# Grilo.net
KiCad netlist of a schematic drawn in EAGLE
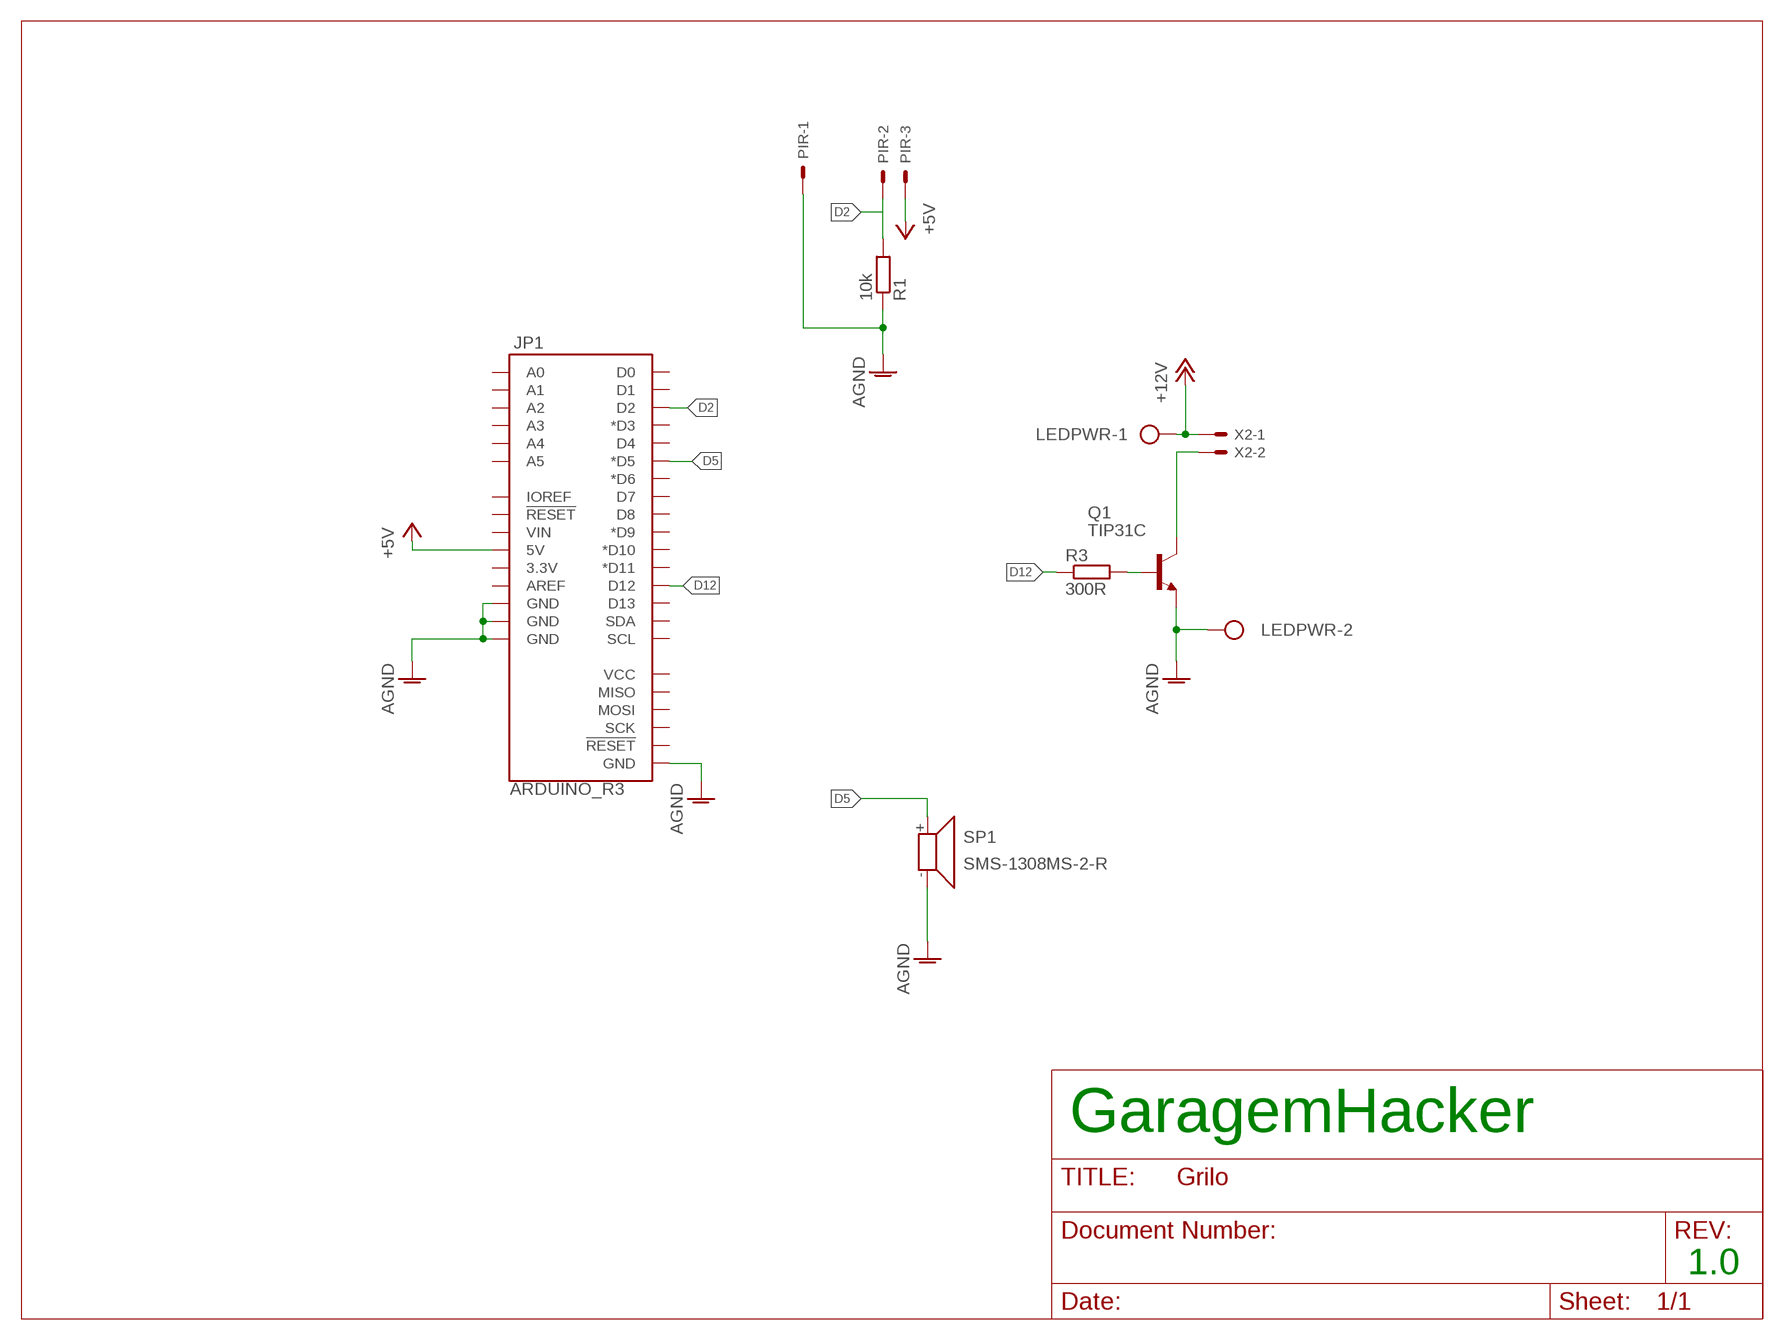
[diagram p0: schematic, sheet 1]

(export (version "E")
  (design (tool "Eeschema 10.0.6"))
  (components
    (comp (ref "JP1")
      (value "ARDUINO_R3")
      (footprint "eagle-import:ARDUINO_R3")
      (libsource (lib "eagle-import") (part "ARDUINO_R3"))
    )
    (comp (ref "LEDPWR")
      (value "AK500/2")
      (footprint "eagle-import:AK500_2")
      (libsource (lib "eagle-import") (part "AK500/2"))
    )
    (comp (ref "PIR")
      (value "KK-156-3")
      (footprint "eagle-import:KK-156-3")
      (libsource (lib "eagle-import") (part "KK-156-3"))
    )
    (comp (ref "Q1")
      (value "TIP31C")
      (footprint "eagle-import:TO220V")
      (libsource (lib "eagle-import") (part "TIP31C"))
    )
    (comp (ref "R1")
      (value "10k")
      (footprint "eagle-import:0207_10")
      (libsource (lib "eagle-import") (part "R-EU_0207/10"))
    )
    (comp (ref "R3")
      (value "300R")
      (footprint "eagle-import:0207_10")
      (libsource (lib "eagle-import") (part "R-EU_0207/10"))
    )
    (comp (ref "SP1")
      (value "SMS-1308MS-2-R")
      (footprint "eagle-import:SMS-1308MS-2-R")
      (libsource (lib "eagle-import") (part "SMS-1308MS-2-R"))
    )
    (comp (ref "X2")
      (value "KK-156-2")
      (footprint "eagle-import:KK-156-2")
      (libsource (lib "eagle-import") (part "KK-156-2"))
    )
  )
  (nets
    (net (code "1") (name "+5V") (class "Default")
      (node (ref "JP1") (pin "5V") (pinfunction "5V_5V") (pintype "bidirectional"))
      (node (ref "PIR") (pin "3") (pinfunction "S_3") (pintype "passive"))
    )
    (net (code "2") (name "+12V") (class "Default")
      (node (ref "LEDPWR") (pin "1") (pinfunction "KL_1") (pintype "passive"))
      (node (ref "X2") (pin "1") (pinfunction "S_1") (pintype "passive"))
    )
    (net (code "3") (name "AGND") (class "Default")
      (node (ref "JP1") (pin "GND@1") (pinfunction "GND_GND@1") (pintype "bidirectional"))
      (node (ref "JP1") (pin "GND@2") (pinfunction "GND_GND@2") (pintype "bidirectional"))
      (node (ref "JP1") (pin "GND@3") (pinfunction "GND_GND@3") (pintype "bidirectional"))
      (node (ref "JP1") (pin "GND@4") (pinfunction "GND_GND@4") (pintype "bidirectional"))
      (node (ref "LEDPWR") (pin "2") (pinfunction "KL_2") (pintype "passive"))
      (node (ref "PIR") (pin "1") (pinfunction "S_1") (pintype "passive"))
      (node (ref "Q1") (pin "3") (pinfunction "E_3") (pintype "passive"))
      (node (ref "R1") (pin "1") (pinfunction "1_1") (pintype "passive"))
      (node (ref "SP1") (pin "-") (pinfunction "2_-") (pintype "passive"))
    )
    (net (code "4") (name "D2") (class "Default")
      (node (ref "JP1") (pin "D2") (pinfunction "D2_D2") (pintype "bidirectional"))
      (node (ref "PIR") (pin "2") (pinfunction "S_2") (pintype "passive"))
      (node (ref "R1") (pin "2") (pinfunction "2_2") (pintype "passive"))
    )
    (net (code "5") (name "D5") (class "Default")
      (node (ref "JP1") (pin "D5") (pinfunction "*D5_D5") (pintype "bidirectional"))
      (node (ref "SP1") (pin "+") (pinfunction "1_+") (pintype "passive"))
    )
    (net (code "6") (name "D12") (class "Default")
      (node (ref "JP1") (pin "D12") (pinfunction "D12_D12") (pintype "bidirectional"))
      (node (ref "R3") (pin "1") (pinfunction "1_1") (pintype "passive"))
    )
    (net (code "7") (name "Net-(Q1-B)") (class "Default")
      (node (ref "Q1") (pin "1") (pinfunction "B_1") (pintype "passive"))
      (node (ref "R3") (pin "2") (pinfunction "2_2") (pintype "passive"))
    )
    (net (code "8") (name "Net-(Q1-C)") (class "Default")
      (node (ref "Q1") (pin "2") (pinfunction "C_2") (pintype "passive"))
      (node (ref "X2") (pin "2") (pinfunction "S_2") (pintype "passive"))
    )
    (net (code "9") (name "unconnected-(JP1-*D3-PadD3)") (class "Default")
      (node (ref "JP1") (pin "D3") (pinfunction "*D3_D3") (pintype "bidirectional"))
    )
    (net (code "10") (name "unconnected-(JP1-*D6-PadD6)") (class "Default")
      (node (ref "JP1") (pin "D6") (pinfunction "*D6_D6") (pintype "bidirectional"))
    )
    (net (code "11") (name "unconnected-(JP1-*D9-PadD9)") (class "Default")
      (node (ref "JP1") (pin "D9") (pinfunction "*D9_D9") (pintype "bidirectional"))
    )
    (net (code "12") (name "unconnected-(JP1-*D10-PadD10)") (class "Default")
      (node (ref "JP1") (pin "D10") (pinfunction "*D10_D10") (pintype "bidirectional"))
    )
    (net (code "13") (name "unconnected-(JP1-*D11-PadD11)") (class "Default")
      (node (ref "JP1") (pin "D11") (pinfunction "*D11_D11") (pintype "bidirectional"))
    )
    (net (code "14") (name "unconnected-(JP1-Pad3.3V)") (class "Default")
      (node (ref "JP1") (pin "3.3V") (pinfunction "3.3V_3.3V") (pintype "bidirectional"))
    )
    (net (code "15") (name "unconnected-(JP1-PadA0)") (class "Default")
      (node (ref "JP1") (pin "A0") (pinfunction "A0_A0") (pintype "bidirectional"))
    )
    (net (code "16") (name "unconnected-(JP1-PadA1)") (class "Default")
      (node (ref "JP1") (pin "A1") (pinfunction "A1_A1") (pintype "bidirectional"))
    )
    (net (code "17") (name "unconnected-(JP1-PadA2)") (class "Default")
      (node (ref "JP1") (pin "A2") (pinfunction "A2_A2") (pintype "bidirectional"))
    )
    (net (code "18") (name "unconnected-(JP1-PadA3)") (class "Default")
      (node (ref "JP1") (pin "A3") (pinfunction "A3_A3") (pintype "bidirectional"))
    )
    (net (code "19") (name "unconnected-(JP1-PadA4)") (class "Default")
      (node (ref "JP1") (pin "A4") (pinfunction "A4_A4") (pintype "bidirectional"))
    )
    (net (code "20") (name "unconnected-(JP1-PadA5)") (class "Default")
      (node (ref "JP1") (pin "A5") (pinfunction "A5_A5") (pintype "bidirectional"))
    )
    (net (code "21") (name "unconnected-(JP1-PadAREF)") (class "Default")
      (node (ref "JP1") (pin "AREF") (pinfunction "AREF_AREF") (pintype "bidirectional"))
    )
    (net (code "22") (name "unconnected-(JP1-PadD0)") (class "Default")
      (node (ref "JP1") (pin "D0") (pinfunction "D0_D0") (pintype "bidirectional"))
    )
    (net (code "23") (name "unconnected-(JP1-PadD1)") (class "Default")
      (node (ref "JP1") (pin "D1") (pinfunction "D1_D1") (pintype "bidirectional"))
    )
    (net (code "24") (name "unconnected-(JP1-PadD4)") (class "Default")
      (node (ref "JP1") (pin "D4") (pinfunction "D4_D4") (pintype "bidirectional"))
    )
    (net (code "25") (name "unconnected-(JP1-PadD7)") (class "Default")
      (node (ref "JP1") (pin "D7") (pinfunction "D7_D7") (pintype "bidirectional"))
    )
    (net (code "26") (name "unconnected-(JP1-PadD8)") (class "Default")
      (node (ref "JP1") (pin "D8") (pinfunction "D8_D8") (pintype "bidirectional"))
    )
    (net (code "27") (name "unconnected-(JP1-PadD13)") (class "Default")
      (node (ref "JP1") (pin "D13") (pinfunction "D13_D13") (pintype "bidirectional"))
    )
    (net (code "28") (name "unconnected-(JP1-PadIOREF)") (class "Default")
      (node (ref "JP1") (pin "IOREF") (pinfunction "IOREF_IOREF") (pintype "bidirectional"))
    )
    (net (code "29") (name "unconnected-(JP1-PadMISO)") (class "Default")
      (node (ref "JP1") (pin "MISO") (pinfunction "MISO_MISO") (pintype "bidirectional"))
    )
    (net (code "30") (name "unconnected-(JP1-PadMOSI)") (class "Default")
      (node (ref "JP1") (pin "MOSI") (pinfunction "MOSI_MOSI") (pintype "bidirectional"))
    )
    (net (code "31") (name "unconnected-(JP1-PadSCK)") (class "Default")
      (node (ref "JP1") (pin "SCK") (pinfunction "SCK_SCK") (pintype "bidirectional"))
    )
    (net (code "32") (name "unconnected-(JP1-PadSCL)") (class "Default")
      (node (ref "JP1") (pin "SCL") (pinfunction "SCL_SCL") (pintype "bidirectional"))
    )
    (net (code "33") (name "unconnected-(JP1-PadSDA)") (class "Default")
      (node (ref "JP1") (pin "SDA") (pinfunction "SDA_SDA") (pintype "bidirectional"))
    )
    (net (code "34") (name "unconnected-(JP1-PadVCC)") (class "Default")
      (node (ref "JP1") (pin "VCC") (pinfunction "VCC_VCC") (pintype "bidirectional"))
    )
    (net (code "35") (name "unconnected-(JP1-PadVIN)") (class "Default")
      (node (ref "JP1") (pin "VIN") (pinfunction "VIN_VIN") (pintype "bidirectional"))
    )
    (net (code "36") (name "unconnected-(JP1-~{RESET}-PadRESET@1)") (class "Default")
      (node (ref "JP1") (pin "RESET@1") (pinfunction "~{RESET}_RESET@1") (pintype "bidirectional"))
    )
    (net (code "37") (name "unconnected-(JP1-~{RESET}-PadRESET@2)") (class "Default")
      (node (ref "JP1") (pin "RESET@2") (pinfunction "~{RESET}_RESET@2") (pintype "bidirectional"))
    )
  )
)
